# MARI_SCH.net
KiCad netlist of a schematic drawn in EAGLE
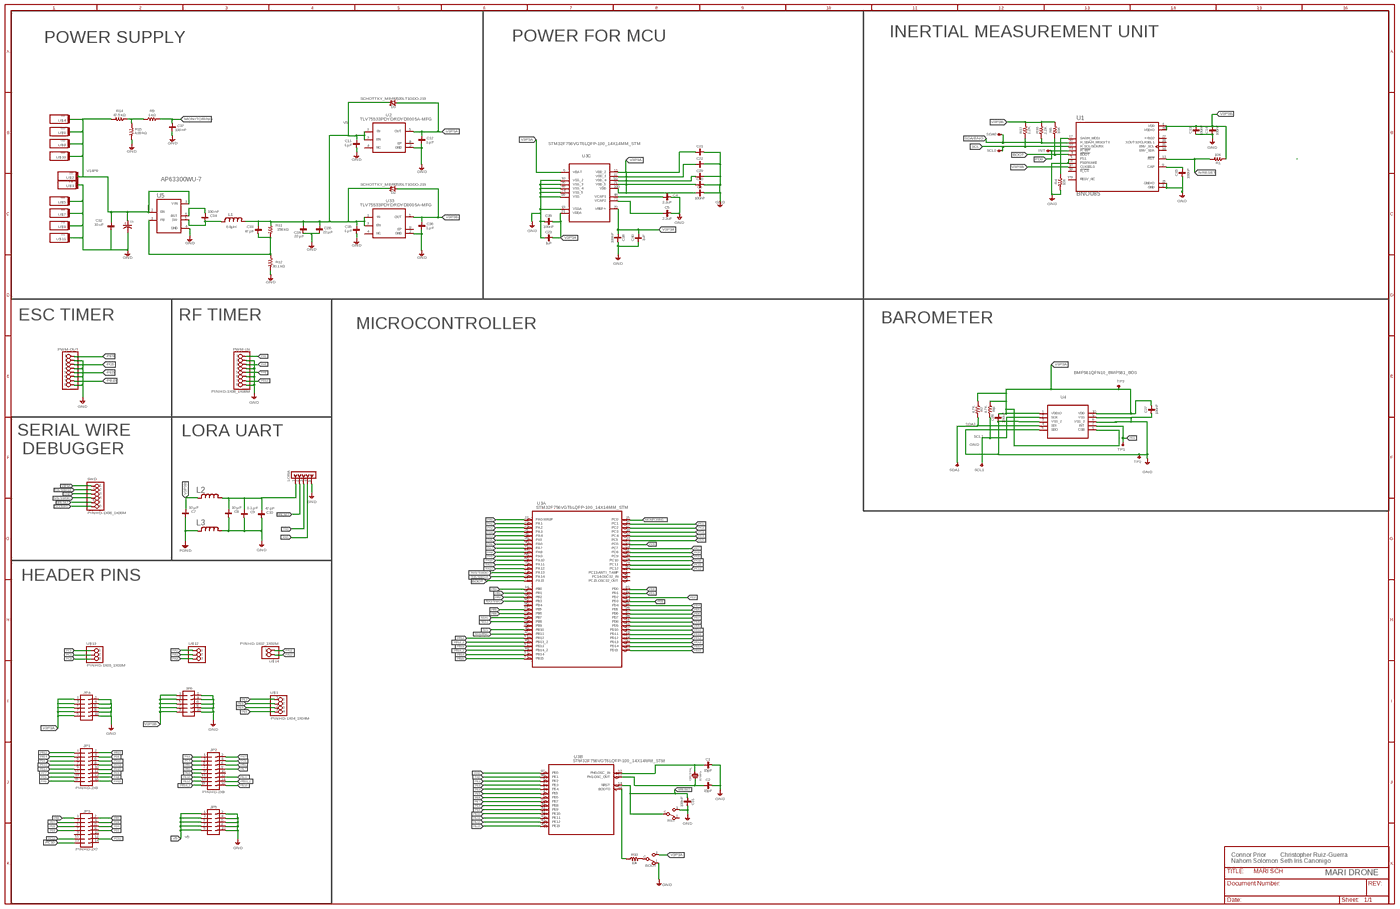
[diagram p0: schematic, sheet 1, overview]
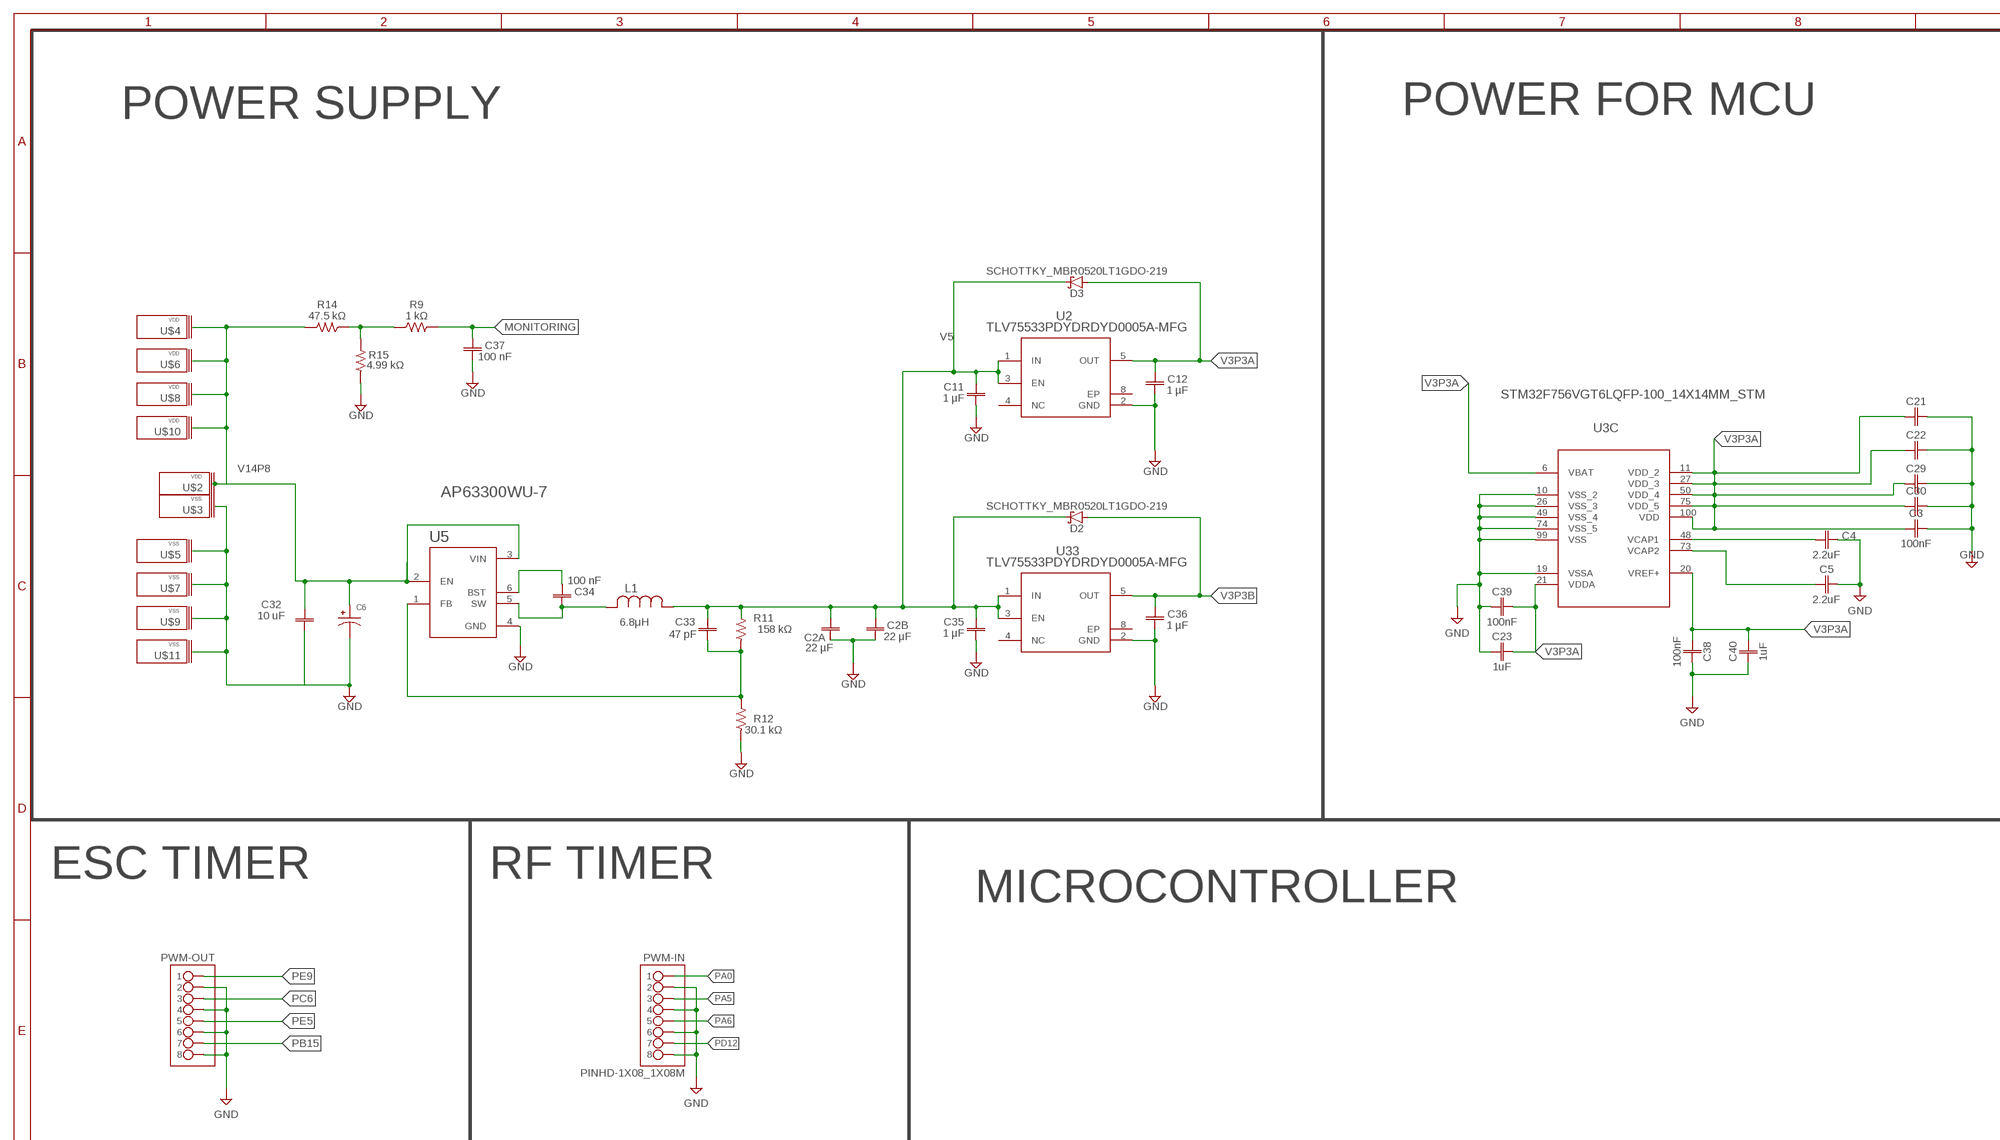
[diagram p1: schematic, sheet 1, part 1 of 4]
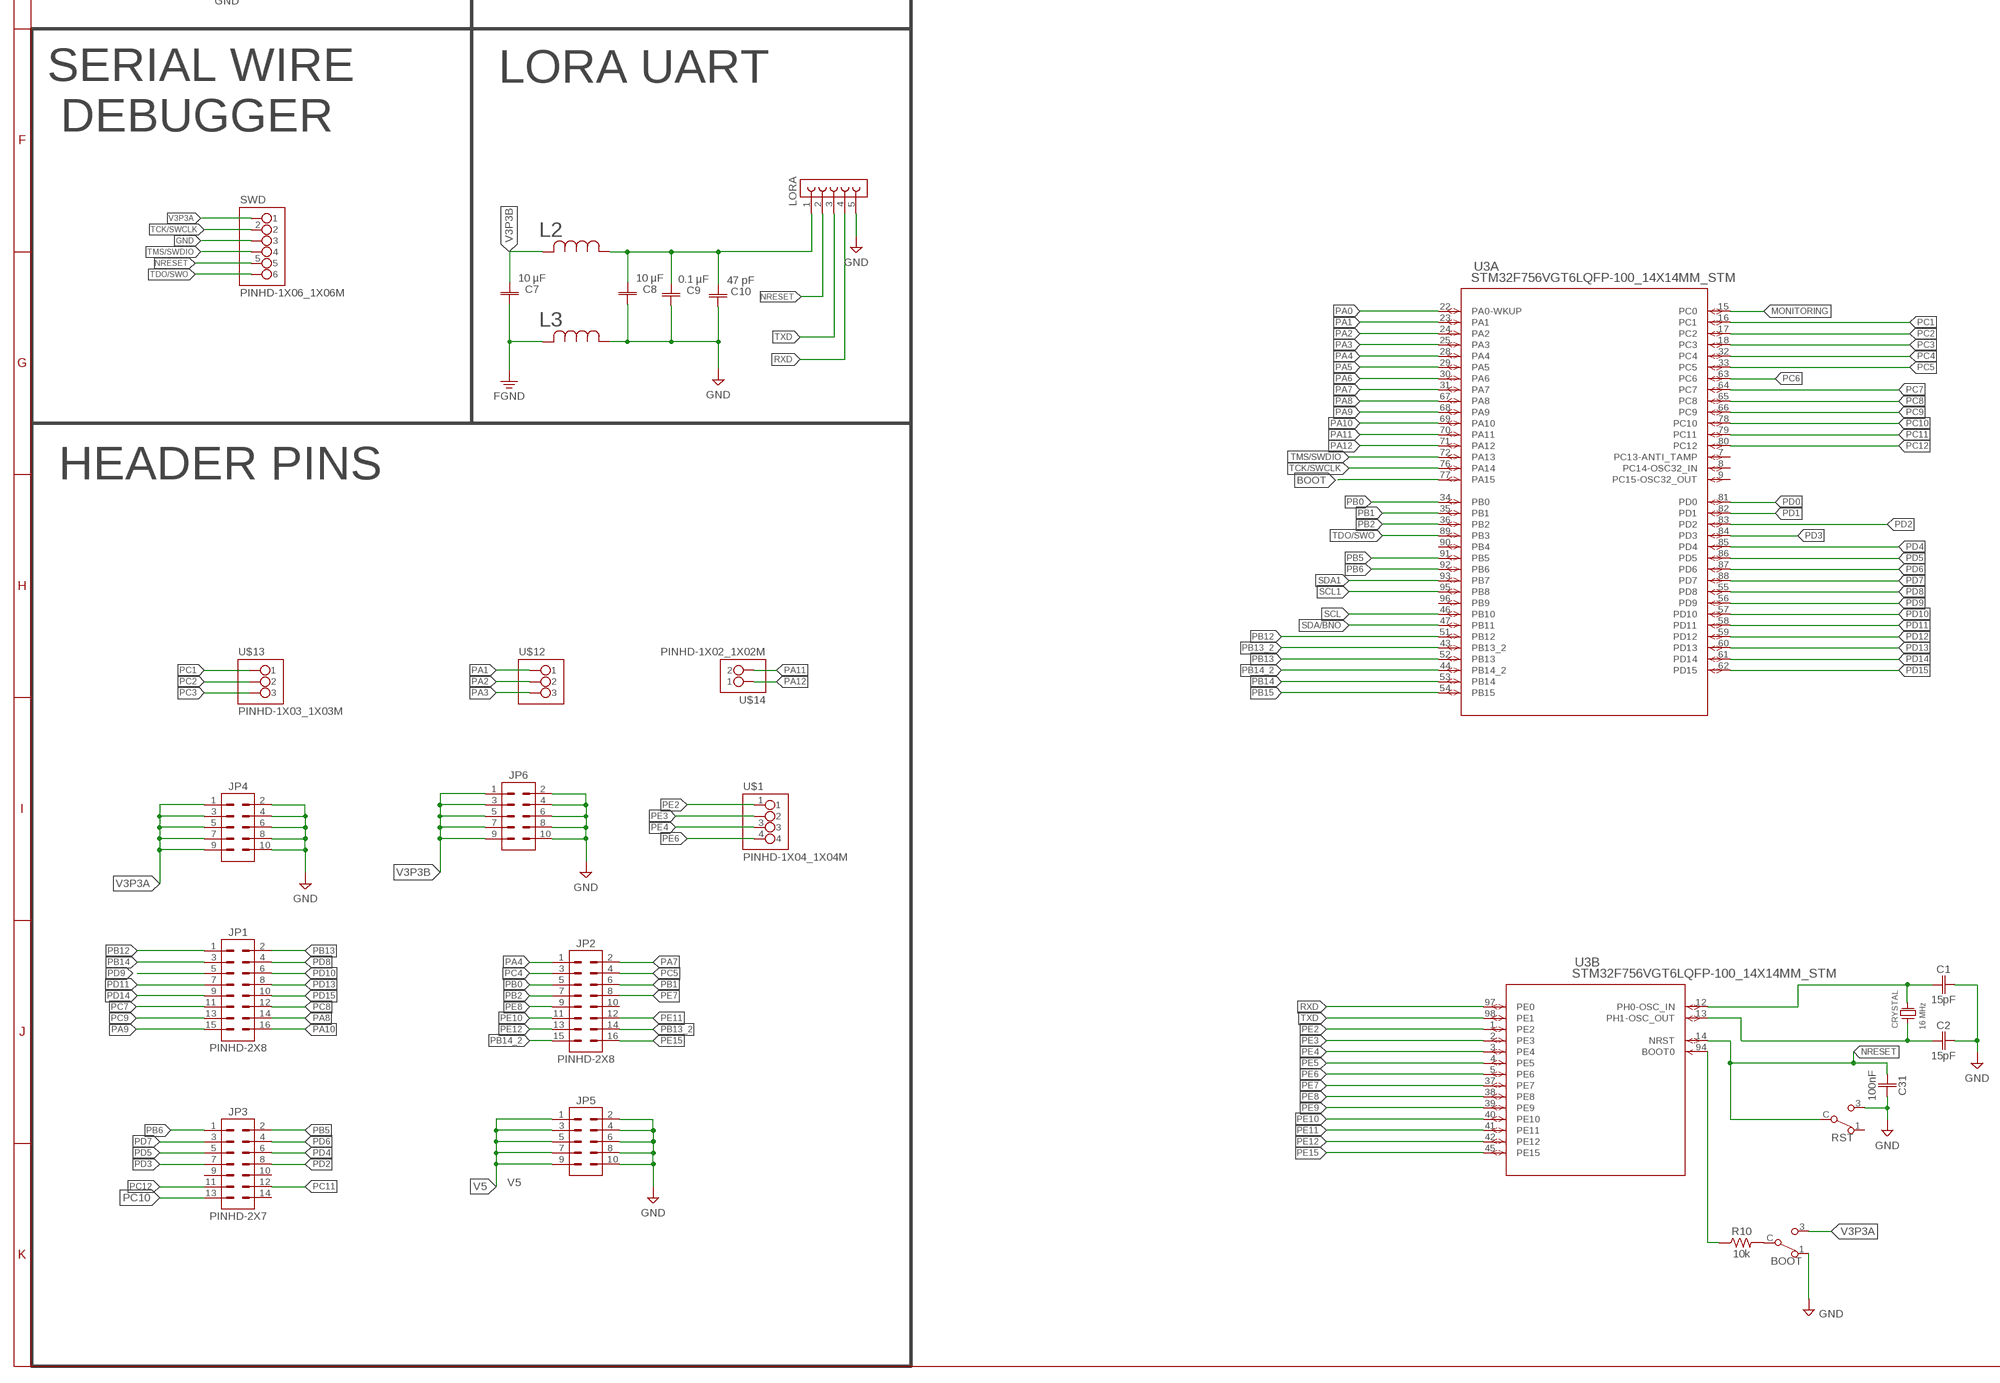
[diagram p2: schematic, sheet 1, part 2 of 4]
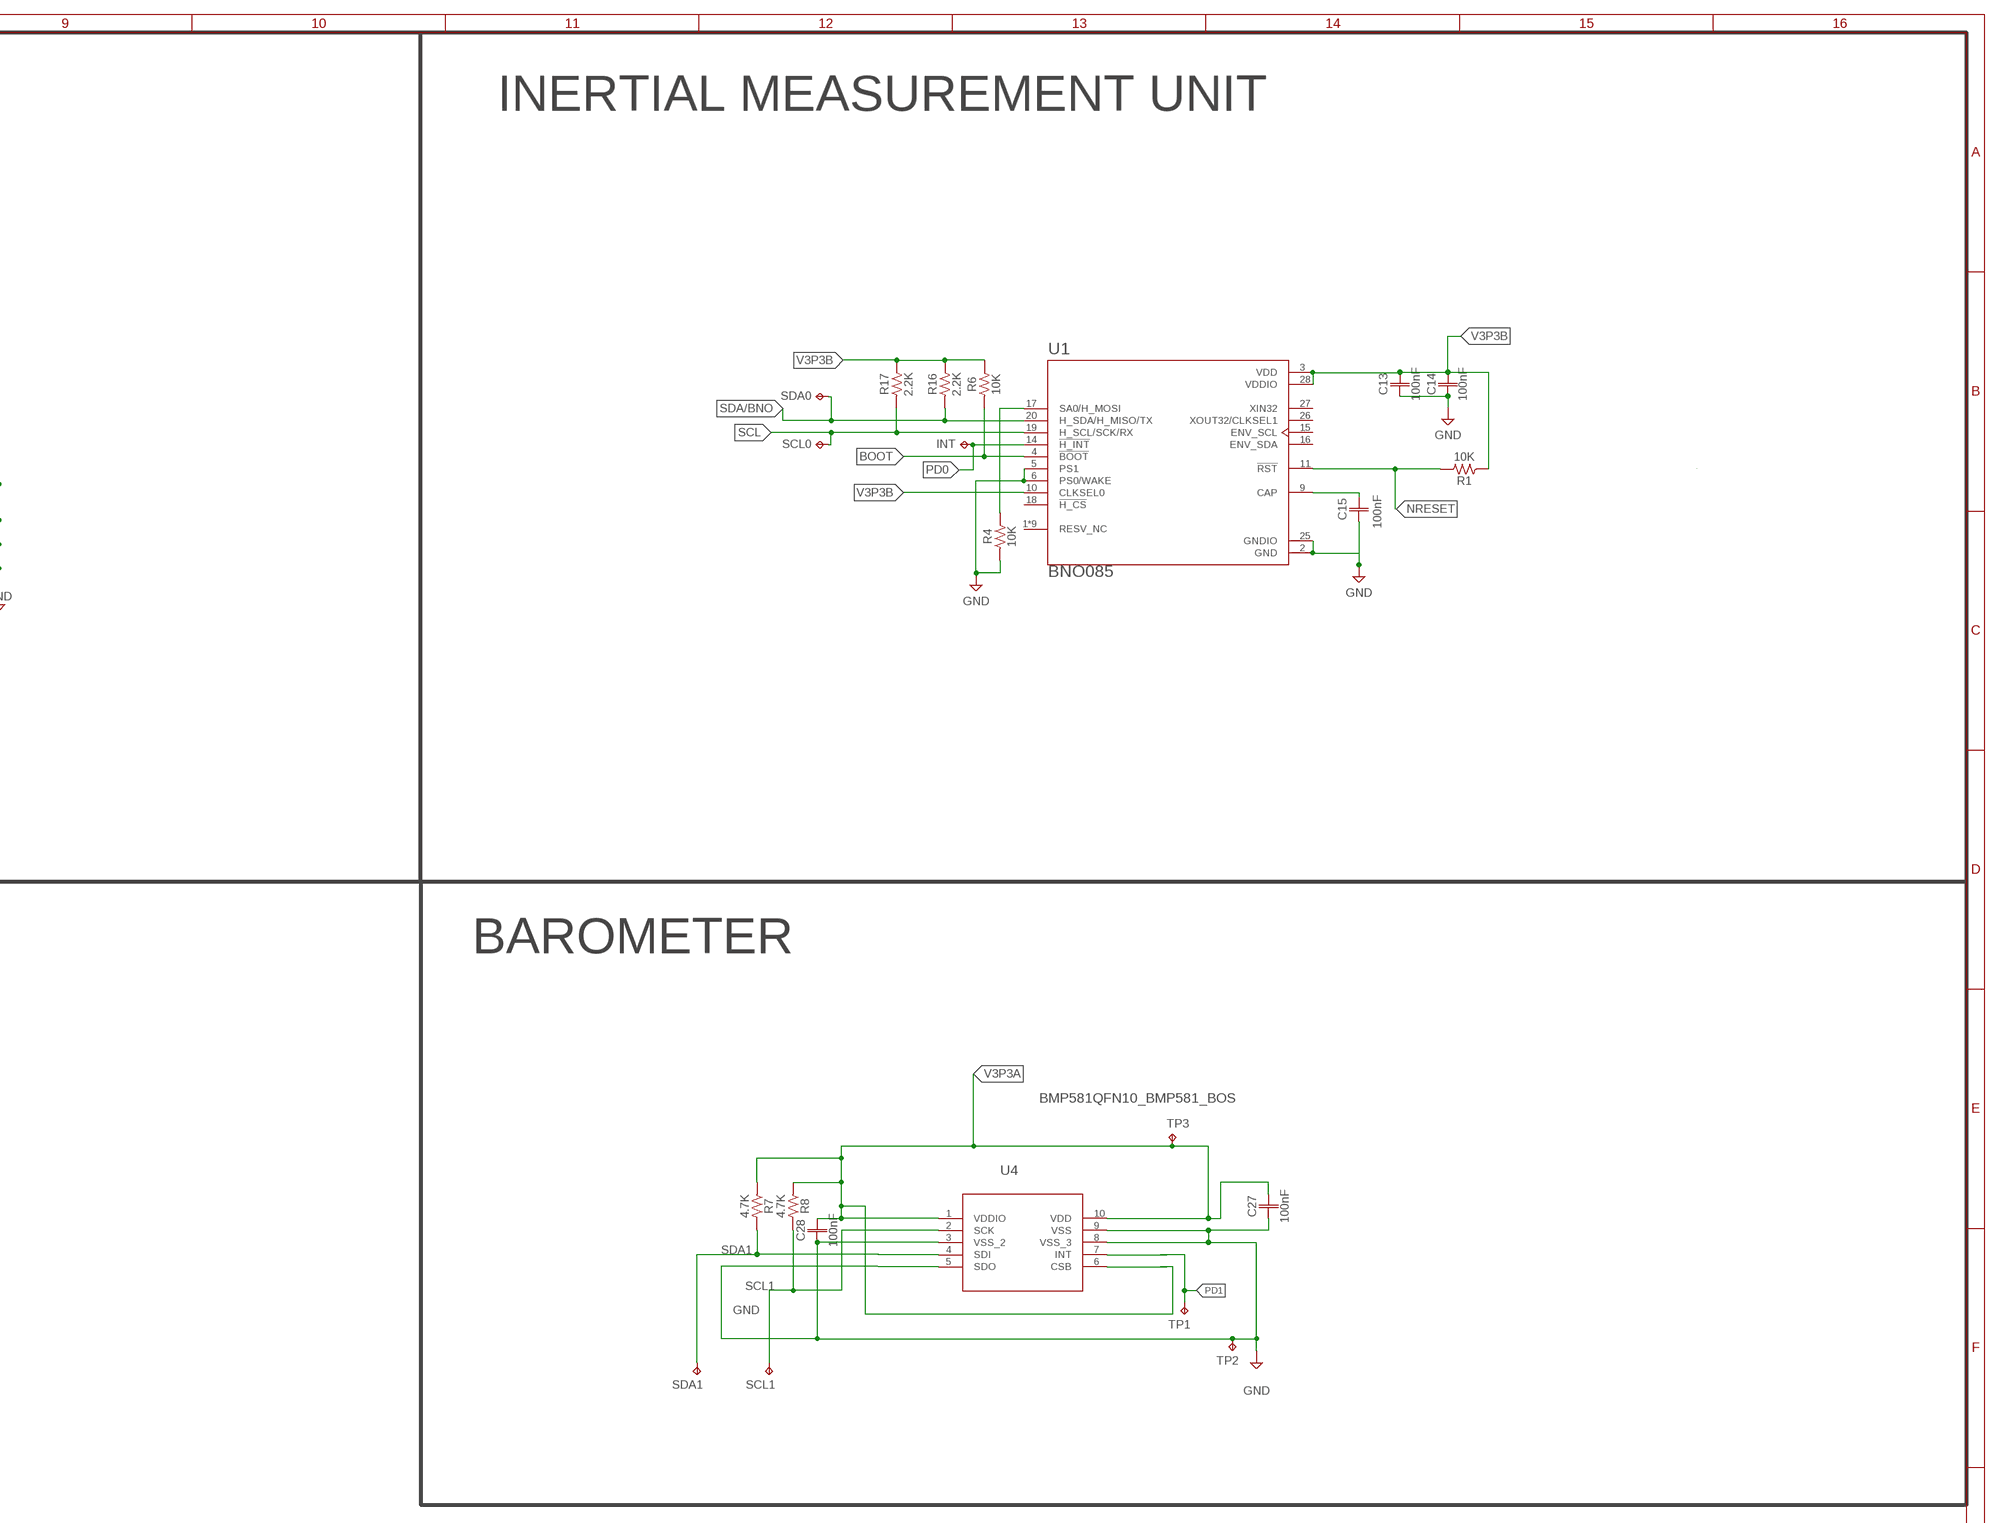
[diagram p3: schematic, sheet 1, part 3 of 4]
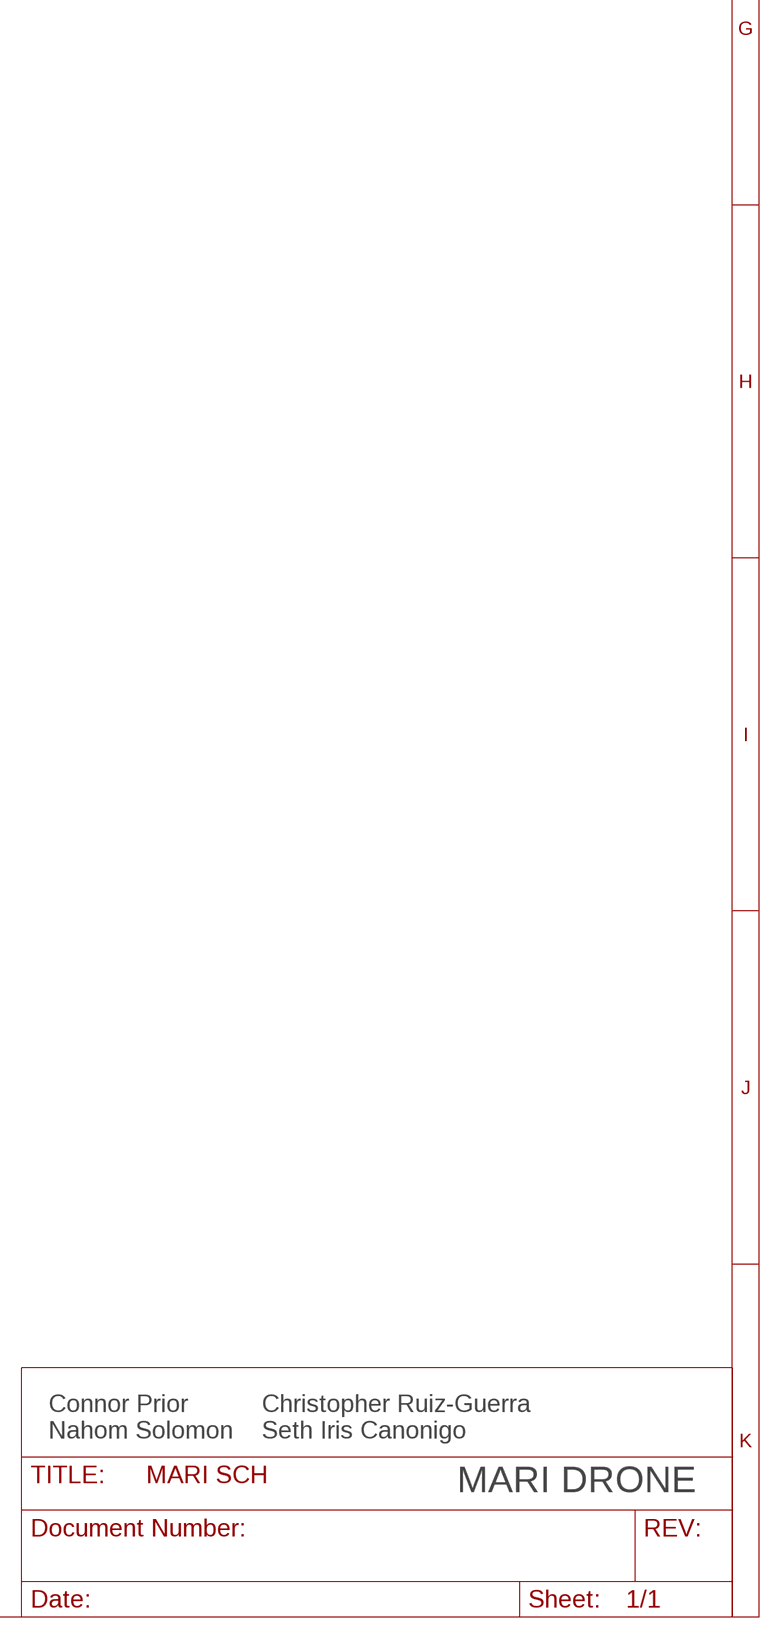
[diagram p4: schematic, sheet 1, part 4 of 4]

(export (version "E")
  (design (tool "Eeschema 10.0.6"))
  (components
    (comp (ref "BOOT")
      (value "SPDT_SWITCH_CL-SB-12B-01T")
      (footprint "eagle-import:CL-SB-12B-01T")
      (fields
        (field (name "MANUFACTURER") "Nidec Components Corporation")
        (field (name "MPN") "CL-SB-12B-01T")
      )
      (libsource (lib "eagle-import") (part "SPDT_SWITCH_CL-SB-12B-01T"))
    )
    (comp (ref "C1")
      (value "15pF")
      (footprint "eagle-import:CAPC1005X60")
      (libsource (lib "eagle-import") (part "CCHIP-0402(1005-METRIC)_"))
    )
    (comp (ref "C2")
      (value "15pF")
      (footprint "eagle-import:CAPC1005X60")
      (libsource (lib "eagle-import") (part "CCHIP-0402(1005-METRIC)_"))
    )
    (comp (ref "C2A")
      (value "22 µF")
      (footprint "eagle-import:CAPC1005X60")
      (libsource (lib "eagle-import") (part "CCHIP-0402(1005-METRIC)_"))
    )
    (comp (ref "C2B")
      (value "22 µF")
      (footprint "eagle-import:CAPC1005X60")
      (libsource (lib "eagle-import") (part "CCHIP-0402(1005-METRIC)_"))
    )
    (comp (ref "C3")
      (value "100nF")
      (footprint "eagle-import:CAPC1005X60")
      (libsource (lib "eagle-import") (part "CCHIP-0402(1005-METRIC)_"))
    )
    (comp (ref "C4")
      (value "2.2uF")
      (footprint "eagle-import:CAPC1005X60")
      (libsource (lib "eagle-import") (part "CCHIP-0402(1005-METRIC)_"))
    )
    (comp (ref "C5")
      (value "2.2uF")
      (footprint "eagle-import:CAPC1005X60")
      (libsource (lib "eagle-import") (part "CCHIP-0402(1005-METRIC)_"))
    )
    (comp (ref "C6")
      (value "B41866C5108M000")
      (footprint "eagle-import:CAPPRD500W60D1250H2200")
      (fields (field (name "MANUFACTURER") "TDK"))
      (libsource (lib "eagle-import") (part "B41866C5108M000"))
    )
    (comp (ref "C7")
      (value "10 µF")
      (footprint "eagle-import:CAPC1005X60")
      (libsource (lib "eagle-import") (part "CCHIP-0402(1005-METRIC)_"))
    )
    (comp (ref "C8")
      (value "10 µF")
      (footprint "eagle-import:CAPC1005X60")
      (libsource (lib "eagle-import") (part "CCHIP-0402(1005-METRIC)_"))
    )
    (comp (ref "C9")
      (value "0.1 µF")
      (footprint "eagle-import:CAPC1005X60")
      (libsource (lib "eagle-import") (part "CCHIP-0402(1005-METRIC)_"))
    )
    (comp (ref "C10")
      (value "47 pF")
      (footprint "eagle-import:CAPC1005X60")
      (libsource (lib "eagle-import") (part "CCHIP-0402(1005-METRIC)_"))
    )
    (comp (ref "C11")
      (value "1 µF")
      (footprint "eagle-import:CAPC1005X60")
      (libsource (lib "eagle-import") (part "CCHIP-0402(1005-METRIC)_"))
    )
    (comp (ref "C12")
      (value "1 µF")
      (footprint "eagle-import:CAPC1005X60")
      (libsource (lib "eagle-import") (part "CCHIP-0402(1005-METRIC)_"))
    )
    (comp (ref "C13")
      (value "100nF")
      (footprint "eagle-import:CAPC1005X60")
      (libsource (lib "eagle-import") (part "CCHIP-0402(1005-METRIC)_"))
    )
    (comp (ref "C14")
      (value "100nF")
      (footprint "eagle-import:CAPC1005X60")
      (libsource (lib "eagle-import") (part "CCHIP-0402(1005-METRIC)_"))
    )
    (comp (ref "C15")
      (value "100nF")
      (footprint "eagle-import:CAPC1005X60")
      (libsource (lib "eagle-import") (part "CCHIP-0402(1005-METRIC)_"))
    )
    (comp (ref "C21")
      (value "100nF")
      (footprint "eagle-import:CAPC1005X60")
      (libsource (lib "eagle-import") (part "CCHIP-0402(1005-METRIC)_"))
    )
    (comp (ref "C22")
      (value "100nF")
      (footprint "eagle-import:CAPC1005X60")
      (libsource (lib "eagle-import") (part "CCHIP-0402(1005-METRIC)_"))
    )
    (comp (ref "C23")
      (value "1uF")
      (footprint "eagle-import:CAPC1005X60")
      (libsource (lib "eagle-import") (part "CCHIP-0402(1005-METRIC)_"))
    )
    (comp (ref "C27")
      (value "100nF")
      (footprint "eagle-import:CAPC1005X60")
      (libsource (lib "eagle-import") (part "CCHIP-0402(1005-METRIC)_"))
    )
    (comp (ref "C28")
      (value "100nF")
      (footprint "eagle-import:CAPC1005X60")
      (libsource (lib "eagle-import") (part "CCHIP-0402(1005-METRIC)_"))
    )
    (comp (ref "C29")
      (value "100nF")
      (footprint "eagle-import:CAPC1005X60")
      (libsource (lib "eagle-import") (part "CCHIP-0402(1005-METRIC)_"))
    )
    (comp (ref "C30")
      (value "100nF")
      (footprint "eagle-import:CAPC1005X60")
      (libsource (lib "eagle-import") (part "CCHIP-0402(1005-METRIC)_"))
    )
    (comp (ref "C31")
      (value "100nF")
      (footprint "eagle-import:CAPC1005X60")
      (libsource (lib "eagle-import") (part "CCHIP-0402(1005-METRIC)_"))
    )
    (comp (ref "C32")
      (value "10 uF")
      (footprint "eagle-import:CAPC2012X110")
      (libsource (lib "eagle-import") (part "CCHIP-0805(2012-METRIC)_"))
    )
    (comp (ref "C33")
      (value "47 pF")
      (footprint "eagle-import:CAPC1005X60")
      (libsource (lib "eagle-import") (part "CCHIP-0402(1005-METRIC)_"))
    )
    (comp (ref "C34")
      (value "100 nF")
      (footprint "eagle-import:CAPC1005X60")
      (libsource (lib "eagle-import") (part "CCHIP-0402(1005-METRIC)_"))
    )
    (comp (ref "C35")
      (value "1 µF")
      (footprint "eagle-import:CAPC1005X60")
      (libsource (lib "eagle-import") (part "CCHIP-0402(1005-METRIC)_"))
    )
    (comp (ref "C36")
      (value "1 µF")
      (footprint "eagle-import:CAPC1005X60")
      (libsource (lib "eagle-import") (part "CCHIP-0402(1005-METRIC)_"))
    )
    (comp (ref "C37")
      (value "100 nF")
      (footprint "eagle-import:CAPC1005X60")
      (libsource (lib "eagle-import") (part "CCHIP-0402(1005-METRIC)_"))
    )
    (comp (ref "C38")
      (value "100nF")
      (footprint "eagle-import:CAPC1005X60")
      (libsource (lib "eagle-import") (part "CCHIP-0402(1005-METRIC)_"))
    )
    (comp (ref "C39")
      (value "100nF")
      (footprint "eagle-import:CAPC1005X60")
      (libsource (lib "eagle-import") (part "CCHIP-0402(1005-METRIC)_"))
    )
    (comp (ref "C40")
      (value "1uF")
      (footprint "eagle-import:CAPC1005X60")
      (libsource (lib "eagle-import") (part "CCHIP-0402(1005-METRIC)_"))
    )
    (comp (ref "CRYSTAL")
      (value "16 MHz")
      (footprint "eagle-import:STDCRG1-16M")
      (libsource (lib "eagle-import") (part "STDCRG1-16M"))
    )
    (comp (ref "D2")
      (value "SCHOTTKY_MBR0520LT1GDO-219")
      (footprint "eagle-import:SODFL3718X115")
      (fields (field (name "MANUFACTURER") "onsemi") (field (name "MPN") "MBR0520LT1G"))
      (libsource (lib "eagle-import") (part "SCHOTTKY_DO-219MBR0520LT1G"))
    )
    (comp (ref "D3")
      (value "SCHOTTKY_MBR0520LT1GDO-219")
      (footprint "eagle-import:SODFL3718X115")
      (fields (field (name "MANUFACTURER") "onsemi") (field (name "MPN") "MBR0520LT1G"))
      (libsource (lib "eagle-import") (part "SCHOTTKY_DO-219MBR0520LT1G"))
    )
    (comp (ref "INT")
      (value "TPB1,27")
      (footprint "eagle-import:B1,27")
      (libsource (lib "eagle-import") (part "TPB1,27"))
    )
    (comp (ref "JP1")
      (value "PINHD-2X8")
      (footprint "eagle-import:2X08")
      (libsource (lib "eagle-import") (part "PINHD-2X8"))
    )
    (comp (ref "JP2")
      (value "PINHD-2X8")
      (footprint "eagle-import:2X08")
      (libsource (lib "eagle-import") (part "PINHD-2X8"))
    )
    (comp (ref "JP3")
      (value "PINHD-2X7")
      (footprint "eagle-import:2X07")
      (libsource (lib "eagle-import") (part "PINHD-2X7"))
    )
    (comp (ref "JP4")
      (value "PINHD-2X5")
      (footprint "eagle-import:2X05")
      (libsource (lib "eagle-import") (part "PINHD-2X5"))
    )
    (comp (ref "JP5")
      (value "PINHD-2X5")
      (footprint "eagle-import:2X05")
      (libsource (lib "eagle-import") (part "PINHD-2X5"))
    )
    (comp (ref "JP6")
      (value "PINHD-2X5")
      (footprint "eagle-import:2X05")
      (libsource (lib "eagle-import") (part "PINHD-2X5"))
    )
    (comp (ref "L1")
      (value "74437334068IND_WE-LHMI_5020_WRE")
      (footprint "eagle-import:IND_WE-LHMI_5020_WRE")
      (fields
        (field (name "MANUFACTURER_PART_NUMBER") "74437334068")
        (field (name "COPYRIGHT") "Copyright (C) 2026 Ultra Librarian. All rights reserved.")
      )
      (libsource (lib "eagle-import") (part "74437334068IND_WE-LHMI_5020_WRE"))
    )
    (comp (ref "L2")
      (value "BLM15EG121SN1DIND_BLM15_0402_MUR-M")
      (footprint "eagle-import:IND_BLM15_0402_MUR-M")
      (fields
        (field (name "MANUFACTURER_PART_NUMBER") "BLM15EG121SN1D")
        (field (name "COPYRIGHT") "Copyright (C) 2026 Ultra Librarian. All rights reserved.")
      )
      (libsource (lib "eagle-import") (part "BLM15EG121SN1DIND_BLM15_0402_MUR-M"))
    )
    (comp (ref "L3")
      (value "BLM15EG121SN1DIND_BLM15_0402_MUR-M")
      (footprint "eagle-import:IND_BLM15_0402_MUR-M")
      (fields
        (field (name "MANUFACTURER_PART_NUMBER") "BLM15EG121SN1D")
        (field (name "COPYRIGHT") "Copyright (C) 2026 Ultra Librarian. All rights reserved.")
      )
      (libsource (lib "eagle-import") (part "BLM15EG121SN1DIND_BLM15_0402_MUR-M"))
    )
    (comp (ref "LORA")
      (value "FEMALE-HEADER-1X5")
      (footprint "eagle-import:1X05")
      (libsource (lib "eagle-import") (part "FEMALE-HEADER-1X5"))
    )
    (comp (ref "PWM-IN")
      (value "PINHD-1X08_1X08M")
      (footprint "eagle-import:1X08")
      (libsource (lib "eagle-import") (part "PINHD-1X08_1X08M"))
    )
    (comp (ref "PWM-OUT")
      (value "PINHD-1X08_1X08M")
      (footprint "eagle-import:1X08")
      (libsource (lib "eagle-import") (part "PINHD-1X08_1X08M"))
    )
    (comp (ref "R1")
      (value "10K")
      (footprint "eagle-import:RESC1005X40")
      (libsource (lib "eagle-import") (part "R-USCHIP-0402(1005-METRIC)_"))
    )
    (comp (ref "R4")
      (value "10K")
      (footprint "eagle-import:RESC1005X40")
      (libsource (lib "eagle-import") (part "R-USCHIP-0402(1005-METRIC)_"))
    )
    (comp (ref "R6")
      (value "10K")
      (footprint "eagle-import:RESC1005X40")
      (libsource (lib "eagle-import") (part "R-USCHIP-0402(1005-METRIC)_"))
    )
    (comp (ref "R7")
      (value "4.7K")
      (footprint "eagle-import:RESC1005X40")
      (libsource (lib "eagle-import") (part "R-USCHIP-0402(1005-METRIC)_"))
    )
    (comp (ref "R8")
      (value "4.7K")
      (footprint "eagle-import:RESC1005X40")
      (libsource (lib "eagle-import") (part "R-USCHIP-0402(1005-METRIC)_"))
    )
    (comp (ref "R9")
      (value "1 kΩ")
      (footprint "eagle-import:RESC1005X40")
      (libsource (lib "eagle-import") (part "R-USCHIP-0402(1005-METRIC)_"))
    )
    (comp (ref "R10")
      (value "10k")
      (footprint "eagle-import:RESC1005X40")
      (libsource (lib "eagle-import") (part "R-USCHIP-0402(1005-METRIC)_"))
    )
    (comp (ref "R11")
      (value "158 kΩ")
      (footprint "eagle-import:RESC1005X40")
      (libsource (lib "eagle-import") (part "R-USCHIP-0402(1005-METRIC)_"))
    )
    (comp (ref "R12")
      (value "30.1 kΩ")
      (footprint "eagle-import:RESC1005X40")
      (libsource (lib "eagle-import") (part "R-USCHIP-0402(1005-METRIC)_"))
    )
    (comp (ref "R14")
      (value "47.5 kΩ")
      (footprint "eagle-import:RESC1005X40")
      (libsource (lib "eagle-import") (part "R-USCHIP-0402(1005-METRIC)_"))
    )
    (comp (ref "R15")
      (value "4.99 kΩ")
      (footprint "eagle-import:RESC1005X40")
      (libsource (lib "eagle-import") (part "R-USCHIP-0402(1005-METRIC)_"))
    )
    (comp (ref "R16")
      (value "2.2K")
      (footprint "eagle-import:RESC1005X40")
      (libsource (lib "eagle-import") (part "R-USCHIP-0402(1005-METRIC)_"))
    )
    (comp (ref "R17")
      (value "2.2K")
      (footprint "eagle-import:RESC1005X40")
      (libsource (lib "eagle-import") (part "R-USCHIP-0402(1005-METRIC)_"))
    )
    (comp (ref "RST")
      (value "SPDT_SWITCH_CL-SB-12B-01T")
      (footprint "eagle-import:CL-SB-12B-01T")
      (fields
        (field (name "MANUFACTURER") "Nidec Components Corporation")
        (field (name "MPN") "CL-SB-12B-01T")
      )
      (libsource (lib "eagle-import") (part "SPDT_SWITCH_CL-SB-12B-01T"))
    )
    (comp (ref "SCL0")
      (value "TPB1,27")
      (footprint "eagle-import:B1,27")
      (libsource (lib "eagle-import") (part "TPB1,27"))
    )
    (comp (ref "SCL1")
      (value "TPB1,27")
      (footprint "eagle-import:B1,27")
      (libsource (lib "eagle-import") (part "TPB1,27"))
    )
    (comp (ref "SDA0")
      (value "TPB1,27")
      (footprint "eagle-import:B1,27")
      (libsource (lib "eagle-import") (part "TPB1,27"))
    )
    (comp (ref "SDA1")
      (value "TPB1,27")
      (footprint "eagle-import:B1,27")
      (libsource (lib "eagle-import") (part "TPB1,27"))
    )
    (comp (ref "SWD")
      (value "PINHD-1X06_1X06M")
      (footprint "eagle-import:1X06")
      (libsource (lib "eagle-import") (part "PINHD-1X06_1X06M"))
    )
    (comp (ref "TP1")
      (value "TPB1,27")
      (footprint "eagle-import:B1,27")
      (libsource (lib "eagle-import") (part "TPB1,27"))
    )
    (comp (ref "TP2")
      (value "TPB1,27")
      (footprint "eagle-import:B1,27")
      (libsource (lib "eagle-import") (part "TPB1,27"))
    )
    (comp (ref "TP3")
      (value "TPB1,27")
      (footprint "eagle-import:B1,27")
      (libsource (lib "eagle-import") (part "TPB1,27"))
    )
    (comp (ref "U$1")
      (value "PINHD-1X04_1X04M")
      (footprint "eagle-import:1X04")
      (libsource (lib "eagle-import") (part "PINHD-1X04_1X04M"))
    )
    (comp (ref "U$2")
      (value "VDD")
      (footprint "eagle-import:4MM_PLUG")
      (libsource (lib "eagle-import") (part "4MM_FEMALE_VDD"))
    )
    (comp (ref "U$3")
      (value "VSS")
      (footprint "eagle-import:4MM_PLUG")
      (libsource (lib "eagle-import") (part "4MM_FEMALE_VSS"))
    )
    (comp (ref "U$4")
      (value "VDD")
      (footprint "eagle-import:4MM_PLUG")
      (libsource (lib "eagle-import") (part "4MM_FEMALE_VDD"))
    )
    (comp (ref "U$5")
      (value "VSS")
      (footprint "eagle-import:4MM_PLUG")
      (libsource (lib "eagle-import") (part "4MM_FEMALE_VSS"))
    )
    (comp (ref "U$6")
      (value "VDD")
      (footprint "eagle-import:4MM_PLUG")
      (libsource (lib "eagle-import") (part "4MM_FEMALE_VDD"))
    )
    (comp (ref "U$7")
      (value "VSS")
      (footprint "eagle-import:4MM_PLUG")
      (libsource (lib "eagle-import") (part "4MM_FEMALE_VSS"))
    )
    (comp (ref "U$8")
      (value "VDD")
      (footprint "eagle-import:4MM_PLUG")
      (libsource (lib "eagle-import") (part "4MM_FEMALE_VDD"))
    )
    (comp (ref "U$9")
      (value "VSS")
      (footprint "eagle-import:4MM_PLUG")
      (libsource (lib "eagle-import") (part "4MM_FEMALE_VSS"))
    )
    (comp (ref "U$10")
      (value "VDD")
      (footprint "eagle-import:4MM_PLUG")
      (libsource (lib "eagle-import") (part "4MM_FEMALE_VDD"))
    )
    (comp (ref "U$11")
      (value "VSS")
      (footprint "eagle-import:4MM_PLUG")
      (libsource (lib "eagle-import") (part "4MM_FEMALE_VSS"))
    )
    (comp (ref "U$12")
      (value "PINHD-1X03_1X03M")
      (footprint "eagle-import:1X03")
      (libsource (lib "eagle-import") (part "PINHD-1X03_1X03M"))
    )
    (comp (ref "U$13")
      (value "PINHD-1X03_1X03M")
      (footprint "eagle-import:1X03")
      (libsource (lib "eagle-import") (part "PINHD-1X03_1X03M"))
    )
    (comp (ref "U$14")
      (value "PINHD-1X02_1X02M")
      (footprint "eagle-import:1X02")
      (libsource (lib "eagle-import") (part "PINHD-1X02_1X02M"))
    )
    (comp (ref "U1")
      (value "BNO085")
      (footprint "eagle-import:IC_BNO085")
      (fields (field (name "MF") "Hillcrest Laboratories,"))
      (libsource (lib "eagle-import") (part "BNO085"))
    )
    (comp (ref "U2")
      (value "TLV75533PDYDRDYD0005A-MFG")
      (footprint "eagle-import:DYD0005A-MFG")
      (fields
        (field (name "MANUFACTURER_PART_NUMBER") "TLV75533PDYDR")
        (field (name "COPYRIGHT") "Copyright (C) 2025 Ultra Librarian. All rights reserved.")
      )
      (libsource (lib "eagle-import") (part "TLV75533PDYDRDYD0005A-MFG"))
    )
    (comp (ref "U3")
      (value "STM32F756VGT6LQFP-100_14X14MM_STM")
      (footprint "eagle-import:LQFP-100_14X14MM_STM")
      (fields
        (field (name "MANUFACTURER_PART_NUMBER") "STM32F756VGT6")
        (field (name "COPYRIGHT") "Copyright (C) 2025 Ultra Librarian. All rights reserved.")
      )
      (libsource (lib "eagle-import") (part "STM32F756VGT6LQFP-100_14X14MM_STM"))
    )
    (comp (ref "U4")
      (value "BMP581QFN10_BMP581_BOS")
      (footprint "eagle-import:QFN10_BMP581_BOS")
      (fields
        (field (name "MANUFACTURER_PART_NUMBER") "BMP581")
        (field (name "COPYRIGHT") "Copyright (C) 2026 Ultra Librarian. All rights reserved.")
      )
      (libsource (lib "eagle-import") (part "BMP581QFN10_BMP581_BOS"))
    )
    (comp (ref "U5")
      (value "AP63300WU-7")
      (footprint "eagle-import:SOT95P280X100-6N")
      (fields (field (name "MANUFACTURER") "DIODES"))
      (libsource (lib "eagle-import") (part "AP63300WU-7"))
    )
    (comp (ref "U33")
      (value "TLV75533PDYDRDYD0005A-MFG")
      (footprint "eagle-import:DYD0005A-MFG")
      (fields
        (field (name "MANUFACTURER_PART_NUMBER") "TLV75533PDYDR")
        (field (name "COPYRIGHT") "Copyright (C) 2025 Ultra Librarian. All rights reserved.")
      )
      (libsource (lib "eagle-import") (part "TLV75533PDYDRDYD0005A-MFG"))
    )
  )
  (nets
    (net (code "1") (name "/V14P8") (class "Default")
      (node (ref "C32") (pin "2") (pinfunction "2_2") (pintype "passive"))
      (node (ref "C6") (pin "1") (pinfunction "1_1") (pintype "passive"))
      (node (ref "R14") (pin "2") (pinfunction "2_2") (pintype "passive"))
      (node (ref "U$10") (pin "P$1") (pinfunction "P$1_P$1") (pintype "bidirectional"))
      (node (ref "U$2") (pin "P$1") (pinfunction "P$1_P$1") (pintype "bidirectional"))
      (node (ref "U$4") (pin "P$1") (pinfunction "P$1_P$1") (pintype "bidirectional"))
      (node (ref "U$6") (pin "P$1") (pinfunction "P$1_P$1") (pintype "bidirectional"))
      (node (ref "U$8") (pin "P$1") (pinfunction "P$1_P$1") (pintype "bidirectional"))
      (node (ref "U5") (pin "2") (pinfunction "EN_2") (pintype "input"))
      (node (ref "U5") (pin "3") (pinfunction "VIN_3") (pintype "power_in"))
    )
    (net (code "2") (name "BOOT") (class "Default")
      (node (ref "R6") (pin "1") (pinfunction "1_1") (pintype "passive"))
      (node (ref "U1") (pin "4") (pinfunction "~{BOOT}_4") (pintype "input"))
      (node (ref "U3") (pin "77") (pinfunction "PA15_77") (pintype "bidirectional"))
    )
    (net (code "3") (name "FGND") (class "Default")
      (node (ref "C7") (pin "1") (pinfunction "1_1") (pintype "passive"))
      (node (ref "L3") (pin "2") (pinfunction "2_2") (pintype "passive"))
    )
    (net (code "4") (name "GND") (class "Default")
      (node (ref "BOOT") (pin "1") (pinfunction "NC_1") (pintype "passive"))
      (node (ref "C1") (pin "2") (pinfunction "2_2") (pintype "passive"))
      (node (ref "C10") (pin "1") (pinfunction "1_1") (pintype "passive"))
      (node (ref "C11") (pin "1") (pinfunction "1_1") (pintype "passive"))
      (node (ref "C12") (pin "1") (pinfunction "1_1") (pintype "passive"))
      (node (ref "C13") (pin "1") (pinfunction "1_1") (pintype "passive"))
      (node (ref "C14") (pin "1") (pinfunction "1_1") (pintype "passive"))
      (node (ref "C15") (pin "1") (pinfunction "1_1") (pintype "passive"))
      (node (ref "C2") (pin "2") (pinfunction "2_2") (pintype "passive"))
      (node (ref "C21") (pin "2") (pinfunction "2_2") (pintype "passive"))
      (node (ref "C22") (pin "2") (pinfunction "2_2") (pintype "passive"))
      (node (ref "C23") (pin "1") (pinfunction "1_1") (pintype "passive"))
      (node (ref "C27") (pin "1") (pinfunction "1_1") (pintype "passive"))
      (node (ref "C28") (pin "1") (pinfunction "1_1") (pintype "passive"))
      (node (ref "C29") (pin "2") (pinfunction "2_2") (pintype "passive"))
      (node (ref "C2A") (pin "2") (pinfunction "2_2") (pintype "passive"))
      (node (ref "C2B") (pin "2") (pinfunction "2_2") (pintype "passive"))
      (node (ref "C3") (pin "2") (pinfunction "2_2") (pintype "passive"))
      (node (ref "C30") (pin "2") (pinfunction "2_2") (pintype "passive"))
      (node (ref "C31") (pin "2") (pinfunction "2_2") (pintype "passive"))
      (node (ref "C32") (pin "1") (pinfunction "1_1") (pintype "passive"))
      (node (ref "C35") (pin "1") (pinfunction "1_1") (pintype "passive"))
      (node (ref "C36") (pin "1") (pinfunction "1_1") (pintype "passive"))
      (node (ref "C37") (pin "2") (pinfunction "2_2") (pintype "passive"))
      (node (ref "C38") (pin "2") (pinfunction "2_2") (pintype "passive"))
      (node (ref "C39") (pin "1") (pinfunction "1_1") (pintype "passive"))
      (node (ref "C4") (pin "2") (pinfunction "2_2") (pintype "passive"))
      (node (ref "C40") (pin "1") (pinfunction "1_1") (pintype "passive"))
      (node (ref "C5") (pin "2") (pinfunction "2_2") (pintype "passive"))
      (node (ref "C6") (pin "2") (pinfunction "2_2") (pintype "passive"))
      (node (ref "C8") (pin "1") (pinfunction "1_1") (pintype "passive"))
      (node (ref "C9") (pin "1") (pinfunction "1_1") (pintype "passive"))
      (node (ref "JP4") (pin "10") (pinfunction "10_10") (pintype "passive"))
      (node (ref "JP4") (pin "2") (pinfunction "2_2") (pintype "passive"))
      (node (ref "JP4") (pin "4") (pinfunction "4_4") (pintype "passive"))
      (node (ref "JP4") (pin "6") (pinfunction "6_6") (pintype "passive"))
      (node (ref "JP4") (pin "8") (pinfunction "8_8") (pintype "passive"))
      (node (ref "JP5") (pin "10") (pinfunction "10_10") (pintype "passive"))
      (node (ref "JP5") (pin "2") (pinfunction "2_2") (pintype "passive"))
      (node (ref "JP5") (pin "4") (pinfunction "4_4") (pintype "passive"))
      (node (ref "JP5") (pin "6") (pinfunction "6_6") (pintype "passive"))
      (node (ref "JP5") (pin "8") (pinfunction "8_8") (pintype "passive"))
      (node (ref "JP6") (pin "10") (pinfunction "10_10") (pintype "passive"))
      (node (ref "JP6") (pin "2") (pinfunction "2_2") (pintype "passive"))
      (node (ref "JP6") (pin "4") (pinfunction "4_4") (pintype "passive"))
      (node (ref "JP6") (pin "6") (pinfunction "6_6") (pintype "passive"))
      (node (ref "JP6") (pin "8") (pinfunction "8_8") (pintype "passive"))
      (node (ref "L3") (pin "1") (pinfunction "1_1") (pintype "passive"))
      (node (ref "LORA") (pin "5") (pinfunction "5_5") (pintype "passive"))
      (node (ref "PWM-IN") (pin "2") (pinfunction "2_2") (pintype "bidirectional"))
      (node (ref "PWM-IN") (pin "4") (pinfunction "4_4") (pintype "bidirectional"))
      (node (ref "PWM-IN") (pin "6") (pinfunction "6_6") (pintype "bidirectional"))
      (node (ref "PWM-IN") (pin "8") (pinfunction "8_8") (pintype "bidirectional"))
      (node (ref "PWM-OUT") (pin "2") (pinfunction "2_2") (pintype "bidirectional"))
      (node (ref "PWM-OUT") (pin "4") (pinfunction "4_4") (pintype "bidirectional"))
      (node (ref "PWM-OUT") (pin "6") (pinfunction "6_6") (pintype "bidirectional"))
      (node (ref "PWM-OUT") (pin "8") (pinfunction "8_8") (pintype "bidirectional"))
      (node (ref "R12") (pin "1") (pinfunction "1_1") (pintype "passive"))
      (node (ref "R15") (pin "1") (pinfunction "1_1") (pintype "passive"))
      (node (ref "R4") (pin "1") (pinfunction "1_1") (pintype "passive"))
      (node (ref "RST") (pin "3") (pinfunction "NO_3") (pintype "passive"))
      (node (ref "SWD") (pin "3") (pinfunction "3_3") (pintype "bidirectional"))
      (node (ref "TP2") (pin "TP") (pinfunction "TP_TP") (pintype "input"))
      (node (ref "U$11") (pin "P$1") (pinfunction "P$1_P$1") (pintype "bidirectional"))
      (node (ref "U$3") (pin "P$1") (pinfunction "P$1_P$1") (pintype "bidirectional"))
      (node (ref "U$5") (pin "P$1") (pinfunction "P$1_P$1") (pintype "bidirectional"))
      (node (ref "U$7") (pin "P$1") (pinfunction "P$1_P$1") (pintype "bidirectional"))
      (node (ref "U$9") (pin "P$1") (pinfunction "P$1_P$1") (pintype "bidirectional"))
      (node (ref "U1") (pin "2") (pinfunction "GND_2") (pintype "power_in"))
      (node (ref "U1") (pin "25") (pinfunction "GNDIO_25") (pintype "power_in"))
      (node (ref "U1") (pin "5") (pinfunction "PS1_5") (pintype "input"))
      (node (ref "U1") (pin "6") (pinfunction "PS0/WAKE_6") (pintype "input"))
      (node (ref "U2") (pin "2") (pinfunction "GND_2") (pintype "power_in"))
      (node (ref "U3") (pin "10") (pinfunction "VSS_2_10") (pintype "power_in"))
      (node (ref "U3") (pin "19") (pinfunction "VSSA_19") (pintype "power_in"))
      (node (ref "U3") (pin "26") (pinfunction "VSS_3_26") (pintype "power_in"))
      (node (ref "U3") (pin "49") (pinfunction "VSS_4_49") (pintype "power_in"))
      (node (ref "U3") (pin "74") (pinfunction "VSS_5_74") (pintype "power_in"))
      (node (ref "U3") (pin "99") (pinfunction "VSS_99") (pintype "power_in"))
      (node (ref "U33") (pin "2") (pinfunction "GND_2") (pintype "power_in"))
      (node (ref "U4") (pin "3") (pinfunction "VSS_2_3") (pintype "passive"))
      (node (ref "U4") (pin "5") (pinfunction "SDO_5") (pintype "passive"))
      (node (ref "U4") (pin "8") (pinfunction "VSS_3_8") (pintype "passive"))
      (node (ref "U4") (pin "9") (pinfunction "VSS_9") (pintype "passive"))
      (node (ref "U5") (pin "4") (pinfunction "GND_4") (pintype "power_in"))
    )
    (net (code "5") (name "MONITORING") (class "Default")
      (node (ref "C37") (pin "1") (pinfunction "1_1") (pintype "passive"))
      (node (ref "R9") (pin "2") (pinfunction "2_2") (pintype "passive"))
      (node (ref "U3") (pin "15") (pinfunction "PC0_15") (pintype "bidirectional"))
    )
    (net (code "6") (name "NRESET") (class "Default")
      (node (ref "C31") (pin "1") (pinfunction "1_1") (pintype "passive"))
      (node (ref "LORA") (pin "2") (pinfunction "2_2") (pintype "passive"))
      (node (ref "R1") (pin "2") (pinfunction "2_2") (pintype "passive"))
      (node (ref "RST") (pin "C") (pinfunction "COM_C") (pintype "passive"))
      (node (ref "SWD") (pin "5") (pinfunction "5_5") (pintype "bidirectional"))
      (node (ref "U1") (pin "11") (pinfunction "~{RST}_11") (pintype "input"))
      (node (ref "U3") (pin "14") (pinfunction "NRST_14") (pintype "bidirectional"))
    )
    (net (code "7") (name "Net-(BOOT-COM)") (class "Default")
      (node (ref "BOOT") (pin "C") (pinfunction "COM_C") (pintype "passive"))
      (node (ref "R10") (pin "2") (pinfunction "2_2") (pintype "passive"))
    )
    (net (code "8") (name "Net-(C10-Pad2)") (class "Default")
      (node (ref "C10") (pin "2") (pinfunction "2_2") (pintype "passive"))
      (node (ref "C8") (pin "2") (pinfunction "2_2") (pintype "passive"))
      (node (ref "C9") (pin "2") (pinfunction "2_2") (pintype "passive"))
      (node (ref "L2") (pin "1") (pinfunction "1_1") (pintype "passive"))
      (node (ref "LORA") (pin "1") (pinfunction "1_1") (pintype "passive"))
    )
    (net (code "9") (name "Net-(R14-Pad1)") (class "Default")
      (node (ref "R14") (pin "1") (pinfunction "1_1") (pintype "passive"))
      (node (ref "R15") (pin "2") (pinfunction "2_2") (pintype "passive"))
      (node (ref "R9") (pin "1") (pinfunction "1_1") (pintype "passive"))
    )
    (net (code "10") (name "Net-(U1-CAP)") (class "Default")
      (node (ref "C15") (pin "2") (pinfunction "2_2") (pintype "passive"))
      (node (ref "U1") (pin "9") (pinfunction "CAP_9") (pintype "passive"))
    )
    (net (code "11") (name "Net-(U1-SA0{slash}H_MOSI)") (class "Default")
      (node (ref "R4") (pin "2") (pinfunction "2_2") (pintype "passive"))
      (node (ref "U1") (pin "17") (pinfunction "SA0/H_MOSI_17") (pintype "input"))
    )
    (net (code "12") (name "Net-(U3B-BOOT0)") (class "Default")
      (node (ref "R10") (pin "1") (pinfunction "1_1") (pintype "passive"))
      (node (ref "U3") (pin "94") (pinfunction "BOOT0_94") (pintype "input"))
    )
    (net (code "13") (name "Net-(U3B-PH0-OSC_IN)") (class "Default")
      (node (ref "C1") (pin "1") (pinfunction "1_1") (pintype "passive"))
      (node (ref "CRYSTAL") (pin "P$3") (pinfunction "P$3_P$3") (pintype "bidirectional"))
      (node (ref "U3") (pin "12") (pinfunction "PH0-OSC_IN_12") (pintype "bidirectional"))
    )
    (net (code "14") (name "Net-(U3B-PH1-OSC_OUT)") (class "Default")
      (node (ref "C2") (pin "1") (pinfunction "1_1") (pintype "passive"))
      (node (ref "CRYSTAL") (pin "P$1") (pinfunction "P$1_P$1") (pintype "bidirectional"))
      (node (ref "U3") (pin "13") (pinfunction "PH1-OSC_OUT_13") (pintype "bidirectional"))
    )
    (net (code "15") (name "Net-(U3C-VCAP1)") (class "Default")
      (node (ref "C4") (pin "1") (pinfunction "1_1") (pintype "passive"))
      (node (ref "U3") (pin "48") (pinfunction "VCAP1_48") (pintype "power_in"))
    )
    (net (code "16") (name "Net-(U3C-VCAP2)") (class "Default")
      (node (ref "C5") (pin "1") (pinfunction "1_1") (pintype "passive"))
      (node (ref "U3") (pin "73") (pinfunction "VCAP2_73") (pintype "power_in"))
    )
    (net (code "17") (name "Net-(U5-BST)") (class "Default")
      (node (ref "C34") (pin "2") (pinfunction "2_2") (pintype "passive"))
      (node (ref "U5") (pin "6") (pinfunction "BST_6") (pintype "input"))
    )
    (net (code "18") (name "Net-(U5-FB)") (class "Default")
      (node (ref "C33") (pin "1") (pinfunction "1_1") (pintype "passive"))
      (node (ref "R11") (pin "1") (pinfunction "1_1") (pintype "passive"))
      (node (ref "R12") (pin "2") (pinfunction "2_2") (pintype "passive"))
      (node (ref "U5") (pin "1") (pinfunction "FB_1") (pintype "input"))
    )
    (net (code "19") (name "Net-(U5-SW)") (class "Default")
      (node (ref "C34") (pin "1") (pinfunction "1_1") (pintype "passive"))
      (node (ref "L1") (pin "2") (pinfunction "2_2") (pintype "passive"))
      (node (ref "U5") (pin "5") (pinfunction "SW_5") (pintype "output"))
    )
    (net (code "20") (name "PA0") (class "Default")
      (node (ref "PWM-IN") (pin "1") (pinfunction "1_1") (pintype "bidirectional"))
      (node (ref "U3") (pin "22") (pinfunction "PA0-WKUP_22") (pintype "bidirectional"))
    )
    (net (code "21") (name "PA1") (class "Default")
      (node (ref "U$12") (pin "1") (pinfunction "1_1") (pintype "bidirectional"))
      (node (ref "U3") (pin "23") (pinfunction "PA1_23") (pintype "bidirectional"))
    )
    (net (code "22") (name "PA2") (class "Default")
      (node (ref "U$12") (pin "2") (pinfunction "2_2") (pintype "bidirectional"))
      (node (ref "U3") (pin "24") (pinfunction "PA2_24") (pintype "bidirectional"))
    )
    (net (code "23") (name "PA3") (class "Default")
      (node (ref "U$12") (pin "3") (pinfunction "3_3") (pintype "bidirectional"))
      (node (ref "U3") (pin "25") (pinfunction "PA3_25") (pintype "bidirectional"))
    )
    (net (code "24") (name "PA4") (class "Default")
      (node (ref "JP2") (pin "1") (pinfunction "1_1") (pintype "passive"))
      (node (ref "U3") (pin "28") (pinfunction "PA4_28") (pintype "bidirectional"))
    )
    (net (code "25") (name "PA5") (class "Default")
      (node (ref "PWM-IN") (pin "3") (pinfunction "3_3") (pintype "bidirectional"))
      (node (ref "U3") (pin "29") (pinfunction "PA5_29") (pintype "bidirectional"))
    )
    (net (code "26") (name "PA6") (class "Default")
      (node (ref "PWM-IN") (pin "5") (pinfunction "5_5") (pintype "bidirectional"))
      (node (ref "U3") (pin "30") (pinfunction "PA6_30") (pintype "bidirectional"))
    )
    (net (code "27") (name "PA7") (class "Default")
      (node (ref "JP2") (pin "2") (pinfunction "2_2") (pintype "passive"))
      (node (ref "U3") (pin "31") (pinfunction "PA7_31") (pintype "bidirectional"))
    )
    (net (code "28") (name "PA8") (class "Default")
      (node (ref "JP1") (pin "14") (pinfunction "14_14") (pintype "passive"))
      (node (ref "U3") (pin "67") (pinfunction "PA8_67") (pintype "bidirectional"))
    )
    (net (code "29") (name "PA9") (class "Default")
      (node (ref "JP1") (pin "15") (pinfunction "15_15") (pintype "passive"))
      (node (ref "U3") (pin "68") (pinfunction "PA9_68") (pintype "bidirectional"))
    )
    (net (code "30") (name "PA10") (class "Default")
      (node (ref "JP1") (pin "16") (pinfunction "16_16") (pintype "passive"))
      (node (ref "U3") (pin "69") (pinfunction "PA10_69") (pintype "bidirectional"))
    )
    (net (code "31") (name "PA11") (class "Default")
      (node (ref "U$14") (pin "2") (pinfunction "2_2") (pintype "bidirectional"))
      (node (ref "U3") (pin "70") (pinfunction "PA11_70") (pintype "bidirectional"))
    )
    (net (code "32") (name "PA12") (class "Default")
      (node (ref "U$14") (pin "1") (pinfunction "1_1") (pintype "bidirectional"))
      (node (ref "U3") (pin "71") (pinfunction "PA12_71") (pintype "bidirectional"))
    )
    (net (code "33") (name "PB0") (class "Default")
      (node (ref "JP2") (pin "5") (pinfunction "5_5") (pintype "passive"))
      (node (ref "U3") (pin "34") (pinfunction "PB0_34") (pintype "bidirectional"))
    )
    (net (code "34") (name "PB1") (class "Default")
      (node (ref "JP2") (pin "6") (pinfunction "6_6") (pintype "passive"))
      (node (ref "U3") (pin "35") (pinfunction "PB1_35") (pintype "bidirectional"))
    )
    (net (code "35") (name "PB2") (class "Default")
      (node (ref "JP2") (pin "7") (pinfunction "7_7") (pintype "passive"))
      (node (ref "U3") (pin "36") (pinfunction "PB2_36") (pintype "bidirectional"))
    )
    (net (code "36") (name "PB5") (class "Default")
      (node (ref "JP3") (pin "2") (pinfunction "2_2") (pintype "passive"))
      (node (ref "U3") (pin "91") (pinfunction "PB5_91") (pintype "bidirectional"))
    )
    (net (code "37") (name "PB6") (class "Default")
      (node (ref "JP3") (pin "1") (pinfunction "1_1") (pintype "passive"))
      (node (ref "U3") (pin "92") (pinfunction "PB6_92") (pintype "bidirectional"))
    )
    (net (code "38") (name "PB12") (class "Default")
      (node (ref "JP1") (pin "1") (pinfunction "1_1") (pintype "passive"))
      (node (ref "U3") (pin "51") (pinfunction "PB12_51") (pintype "bidirectional"))
    )
    (net (code "39") (name "PB13") (class "Default")
      (node (ref "JP1") (pin "2") (pinfunction "2_2") (pintype "passive"))
      (node (ref "U3") (pin "52") (pinfunction "PB13_52") (pintype "bidirectional"))
    )
    (net (code "40") (name "PB13_2") (class "Default")
      (node (ref "JP2") (pin "14") (pinfunction "14_14") (pintype "passive"))
      (node (ref "U3") (pin "43") (pinfunction "PB13_2_43") (pintype "bidirectional"))
    )
    (net (code "41") (name "PB14") (class "Default")
      (node (ref "JP1") (pin "3") (pinfunction "3_3") (pintype "passive"))
      (node (ref "U3") (pin "53") (pinfunction "PB14_53") (pintype "bidirectional"))
    )
    (net (code "42") (name "PB14_2") (class "Default")
      (node (ref "JP2") (pin "15") (pinfunction "15_15") (pintype "passive"))
      (node (ref "U3") (pin "44") (pinfunction "PB14_2_44") (pintype "bidirectional"))
    )
    (net (code "43") (name "PB15") (class "Default")
      (node (ref "PWM-OUT") (pin "7") (pinfunction "7_7") (pintype "bidirectional"))
      (node (ref "U3") (pin "54") (pinfunction "PB15_54") (pintype "bidirectional"))
    )
    (net (code "44") (name "PC1") (class "Default")
      (node (ref "U$13") (pin "1") (pinfunction "1_1") (pintype "bidirectional"))
      (node (ref "U3") (pin "16") (pinfunction "PC1_16") (pintype "bidirectional"))
    )
    (net (code "45") (name "PC2") (class "Default")
      (node (ref "U$13") (pin "2") (pinfunction "2_2") (pintype "bidirectional"))
      (node (ref "U3") (pin "17") (pinfunction "PC2_17") (pintype "bidirectional"))
    )
    (net (code "46") (name "PC3") (class "Default")
      (node (ref "U$13") (pin "3") (pinfunction "3_3") (pintype "bidirectional"))
      (node (ref "U3") (pin "18") (pinfunction "PC3_18") (pintype "bidirectional"))
    )
    (net (code "47") (name "PC4") (class "Default")
      (node (ref "JP2") (pin "3") (pinfunction "3_3") (pintype "passive"))
      (node (ref "U3") (pin "32") (pinfunction "PC4_32") (pintype "bidirectional"))
    )
    (net (code "48") (name "PC5") (class "Default")
      (node (ref "JP2") (pin "4") (pinfunction "4_4") (pintype "passive"))
      (node (ref "U3") (pin "33") (pinfunction "PC5_33") (pintype "bidirectional"))
    )
    (net (code "49") (name "PC6") (class "Default")
      (node (ref "PWM-OUT") (pin "3") (pinfunction "3_3") (pintype "bidirectional"))
      (node (ref "U3") (pin "63") (pinfunction "PC6_63") (pintype "bidirectional"))
    )
    (net (code "50") (name "PC7") (class "Default")
      (node (ref "JP1") (pin "11") (pinfunction "11_11") (pintype "passive"))
      (node (ref "U3") (pin "64") (pinfunction "PC7_64") (pintype "bidirectional"))
    )
    (net (code "51") (name "PC8") (class "Default")
      (node (ref "JP1") (pin "12") (pinfunction "12_12") (pintype "passive"))
      (node (ref "U3") (pin "65") (pinfunction "PC8_65") (pintype "bidirectional"))
    )
    (net (code "52") (name "PC9") (class "Default")
      (node (ref "JP1") (pin "13") (pinfunction "13_13") (pintype "passive"))
      (node (ref "U3") (pin "66") (pinfunction "PC9_66") (pintype "bidirectional"))
    )
    (net (code "53") (name "PC10") (class "Default")
      (node (ref "JP3") (pin "13") (pinfunction "13_13") (pintype "passive"))
      (node (ref "U3") (pin "78") (pinfunction "PC10_78") (pintype "bidirectional"))
    )
    (net (code "54") (name "PC11") (class "Default")
      (node (ref "JP3") (pin "12") (pinfunction "12_12") (pintype "passive"))
      (node (ref "U3") (pin "79") (pinfunction "PC11_79") (pintype "bidirectional"))
    )
    (net (code "55") (name "PC12") (class "Default")
      (node (ref "JP3") (pin "11") (pinfunction "11_11") (pintype "passive"))
      (node (ref "U3") (pin "80") (pinfunction "PC12_80") (pintype "bidirectional"))
    )
    (net (code "56") (name "PD0") (class "Default")
      (node (ref "INT") (pin "TP") (pinfunction "TP_TP") (pintype "input"))
      (node (ref "U1") (pin "14") (pinfunction "~{H_INT}_14") (pintype "output"))
      (node (ref "U3") (pin "81") (pinfunction "PD0_81") (pintype "bidirectional"))
    )
    (net (code "57") (name "PD1") (class "Default")
      (node (ref "TP1") (pin "TP") (pinfunction "TP_TP") (pintype "input"))
      (node (ref "U3") (pin "82") (pinfunction "PD1_82") (pintype "bidirectional"))
      (node (ref "U4") (pin "7") (pinfunction "INT_7") (pintype "input"))
    )
    (net (code "58") (name "PD2") (class "Default")
      (node (ref "JP3") (pin "8") (pinfunction "8_8") (pintype "passive"))
      (node (ref "U3") (pin "83") (pinfunction "PD2_83") (pintype "bidirectional"))
    )
    (net (code "59") (name "PD3") (class "Default")
      (node (ref "JP3") (pin "7") (pinfunction "7_7") (pintype "passive"))
      (node (ref "U3") (pin "84") (pinfunction "PD3_84") (pintype "bidirectional"))
    )
    (net (code "60") (name "PD4") (class "Default")
      (node (ref "JP3") (pin "6") (pinfunction "6_6") (pintype "passive"))
      (node (ref "U3") (pin "85") (pinfunction "PD4_85") (pintype "bidirectional"))
    )
    (net (code "61") (name "PD5") (class "Default")
      (node (ref "JP3") (pin "5") (pinfunction "5_5") (pintype "passive"))
      (node (ref "U3") (pin "86") (pinfunction "PD5_86") (pintype "bidirectional"))
    )
    (net (code "62") (name "PD6") (class "Default")
      (node (ref "JP3") (pin "4") (pinfunction "4_4") (pintype "passive"))
      (node (ref "U3") (pin "87") (pinfunction "PD6_87") (pintype "bidirectional"))
    )
    (net (code "63") (name "PD7") (class "Default")
      (node (ref "JP3") (pin "3") (pinfunction "3_3") (pintype "passive"))
      (node (ref "U3") (pin "88") (pinfunction "PD7_88") (pintype "bidirectional"))
    )
    (net (code "64") (name "PD8") (class "Default")
      (node (ref "JP1") (pin "4") (pinfunction "4_4") (pintype "passive"))
      (node (ref "U3") (pin "55") (pinfunction "PD8_55") (pintype "bidirectional"))
    )
    (net (code "65") (name "PD9") (class "Default")
      (node (ref "JP1") (pin "5") (pinfunction "5_5") (pintype "passive"))
      (node (ref "U3") (pin "56") (pinfunction "PD9_56") (pintype "bidirectional"))
    )
    (net (code "66") (name "PD10") (class "Default")
      (node (ref "JP1") (pin "6") (pinfunction "6_6") (pintype "passive"))
      (node (ref "U3") (pin "57") (pinfunction "PD10_57") (pintype "bidirectional"))
    )
    (net (code "67") (name "PD11") (class "Default")
      (node (ref "JP1") (pin "7") (pinfunction "7_7") (pintype "passive"))
      (node (ref "U3") (pin "58") (pinfunction "PD11_58") (pintype "bidirectional"))
    )
    (net (code "68") (name "PD12") (class "Default")
      (node (ref "PWM-IN") (pin "7") (pinfunction "7_7") (pintype "bidirectional"))
      (node (ref "U3") (pin "59") (pinfunction "PD12_59") (pintype "bidirectional"))
    )
    (net (code "69") (name "PD13") (class "Default")
      (node (ref "JP1") (pin "8") (pinfunction "8_8") (pintype "passive"))
      (node (ref "U3") (pin "60") (pinfunction "PD13_60") (pintype "bidirectional"))
    )
    (net (code "70") (name "PD14") (class "Default")
      (node (ref "JP1") (pin "9") (pinfunction "9_9") (pintype "passive"))
      (node (ref "U3") (pin "61") (pinfunction "PD14_61") (pintype "bidirectional"))
    )
    (net (code "71") (name "PD15") (class "Default")
      (node (ref "JP1") (pin "10") (pinfunction "10_10") (pintype "passive"))
      (node (ref "U3") (pin "62") (pinfunction "PD15_62") (pintype "bidirectional"))
    )
    (net (code "72") (name "PE2") (class "Default")
      (node (ref "U$1") (pin "1") (pinfunction "1_1") (pintype "bidirectional"))
      (node (ref "U3") (pin "1") (pinfunction "PE2_1") (pintype "bidirectional"))
    )
    (net (code "73") (name "PE3") (class "Default")
      (node (ref "U$1") (pin "2") (pinfunction "2_2") (pintype "bidirectional"))
      (node (ref "U3") (pin "2") (pinfunction "PE3_2") (pintype "bidirectional"))
    )
    (net (code "74") (name "PE4") (class "Default")
      (node (ref "U$1") (pin "3") (pinfunction "3_3") (pintype "bidirectional"))
      (node (ref "U3") (pin "3") (pinfunction "PE4_3") (pintype "bidirectional"))
    )
    (net (code "75") (name "PE5") (class "Default")
      (node (ref "PWM-OUT") (pin "5") (pinfunction "5_5") (pintype "bidirectional"))
      (node (ref "U3") (pin "4") (pinfunction "PE5_4") (pintype "bidirectional"))
    )
    (net (code "76") (name "PE6") (class "Default")
      (node (ref "U$1") (pin "4") (pinfunction "4_4") (pintype "bidirectional"))
      (node (ref "U3") (pin "5") (pinfunction "PE6_5") (pintype "bidirectional"))
    )
    (net (code "77") (name "PE7") (class "Default")
      (node (ref "JP2") (pin "8") (pinfunction "8_8") (pintype "passive"))
      (node (ref "U3") (pin "37") (pinfunction "PE7_37") (pintype "bidirectional"))
    )
    (net (code "78") (name "PE8") (class "Default")
      (node (ref "JP2") (pin "9") (pinfunction "9_9") (pintype "passive"))
      (node (ref "U3") (pin "38") (pinfunction "PE8_38") (pintype "bidirectional"))
    )
    (net (code "79") (name "PE9") (class "Default")
      (node (ref "PWM-OUT") (pin "1") (pinfunction "1_1") (pintype "bidirectional"))
      (node (ref "U3") (pin "39") (pinfunction "PE9_39") (pintype "bidirectional"))
    )
    (net (code "80") (name "PE10") (class "Default")
      (node (ref "JP2") (pin "11") (pinfunction "11_11") (pintype "passive"))
      (node (ref "U3") (pin "40") (pinfunction "PE10_40") (pintype "bidirectional"))
    )
    (net (code "81") (name "PE11") (class "Default")
      (node (ref "JP2") (pin "12") (pinfunction "12_12") (pintype "passive"))
      (node (ref "U3") (pin "41") (pinfunction "PE11_41") (pintype "bidirectional"))
    )
    (net (code "82") (name "PE12") (class "Default")
      (node (ref "JP2") (pin "13") (pinfunction "13_13") (pintype "passive"))
      (node (ref "U3") (pin "42") (pinfunction "PE12_42") (pintype "bidirectional"))
    )
    (net (code "83") (name "PE15") (class "Default")
      (node (ref "JP2") (pin "16") (pinfunction "16_16") (pintype "passive"))
      (node (ref "U3") (pin "45") (pinfunction "PE15_45") (pintype "bidirectional"))
    )
    (net (code "84") (name "RXD") (class "Default")
      (node (ref "LORA") (pin "4") (pinfunction "4_4") (pintype "passive"))
      (node (ref "U3") (pin "97") (pinfunction "PE0_97") (pintype "bidirectional"))
    )
    (net (code "85") (name "SCL") (class "Default")
      (node (ref "R17") (pin "1") (pinfunction "1_1") (pintype "passive"))
      (node (ref "SCL0") (pin "TP") (pinfunction "TP_TP") (pintype "input"))
      (node (ref "U1") (pin "19") (pinfunction "H_SCL/SCK/RX_19") (pintype "bidirectional"))
      (node (ref "U3") (pin "46") (pinfunction "PB10_46") (pintype "bidirectional"))
    )
    (net (code "86") (name "SCL1") (class "Default")
      (node (ref "R8") (pin "2") (pinfunction "2_2") (pintype "passive"))
      (node (ref "SCL1") (pin "TP") (pinfunction "TP_TP") (pintype "input"))
      (node (ref "U3") (pin "95") (pinfunction "PB8_95") (pintype "bidirectional"))
      (node (ref "U4") (pin "2") (pinfunction "SCK_2") (pintype "passive"))
    )
    (net (code "87") (name "SDA1") (class "Default")
      (node (ref "R7") (pin "2") (pinfunction "2_2") (pintype "passive"))
      (node (ref "SDA1") (pin "TP") (pinfunction "TP_TP") (pintype "input"))
      (node (ref "U3") (pin "93") (pinfunction "PB7_93") (pintype "bidirectional"))
      (node (ref "U4") (pin "4") (pinfunction "SDI_4") (pintype "passive"))
    )
    (net (code "88") (name "SDA{slash}BNO") (class "Default")
      (node (ref "R16") (pin "1") (pinfunction "1_1") (pintype "passive"))
      (node (ref "SDA0") (pin "TP") (pinfunction "TP_TP") (pintype "input"))
      (node (ref "U1") (pin "20") (pinfunction "H_SDA/H_MISO/TX_20") (pintype "bidirectional"))
      (node (ref "U3") (pin "47") (pinfunction "PB11_47") (pintype "bidirectional"))
    )
    (net (code "89") (name "TCK{slash}SWCLK") (class "Default")
      (node (ref "SWD") (pin "2") (pinfunction "2_2") (pintype "bidirectional"))
      (node (ref "U3") (pin "76") (pinfunction "PA14_76") (pintype "bidirectional"))
    )
    (net (code "90") (name "TDO{slash}SWO") (class "Default")
      (node (ref "SWD") (pin "6") (pinfunction "6_6") (pintype "bidirectional"))
      (node (ref "U3") (pin "89") (pinfunction "PB3_89") (pintype "bidirectional"))
    )
    (net (code "91") (name "TMS{slash}SWDIO") (class "Default")
      (node (ref "SWD") (pin "4") (pinfunction "4_4") (pintype "bidirectional"))
      (node (ref "U3") (pin "72") (pinfunction "PA13_72") (pintype "bidirectional"))
    )
    (net (code "92") (name "TXD") (class "Default")
      (node (ref "LORA") (pin "3") (pinfunction "3_3") (pintype "passive"))
      (node (ref "U3") (pin "98") (pinfunction "PE1_98") (pintype "bidirectional"))
    )
    (net (code "93") (name "V3P3A") (class "Default")
      (node (ref "BOOT") (pin "3") (pinfunction "NO_3") (pintype "passive"))
      (node (ref "C12") (pin "2") (pinfunction "2_2") (pintype "passive"))
      (node (ref "C21") (pin "1") (pinfunction "1_1") (pintype "passive"))
      (node (ref "C22") (pin "1") (pinfunction "1_1") (pintype "passive"))
      (node (ref "C23") (pin "2") (pinfunction "2_2") (pintype "passive"))
      (node (ref "C27") (pin "2") (pinfunction "2_2") (pintype "passive"))
      (node (ref "C28") (pin "2") (pinfunction "2_2") (pintype "passive"))
      (node (ref "C29") (pin "1") (pinfunction "1_1") (pintype "passive"))
      (node (ref "C3") (pin "1") (pinfunction "1_1") (pintype "passive"))
      (node (ref "C30") (pin "1") (pinfunction "1_1") (pintype "passive"))
      (node (ref "C38") (pin "1") (pinfunction "1_1") (pintype "passive"))
      (node (ref "C39") (pin "2") (pinfunction "2_2") (pintype "passive"))
      (node (ref "C40") (pin "2") (pinfunction "2_2") (pintype "passive"))
      (node (ref "D3") (pin "2") (pinfunction "A_2") (pintype "passive"))
      (node (ref "JP4") (pin "1") (pinfunction "1_1") (pintype "passive"))
      (node (ref "JP4") (pin "3") (pinfunction "3_3") (pintype "passive"))
      (node (ref "JP4") (pin "5") (pinfunction "5_5") (pintype "passive"))
      (node (ref "JP4") (pin "7") (pinfunction "7_7") (pintype "passive"))
      (node (ref "JP4") (pin "9") (pinfunction "9_9") (pintype "passive"))
      (node (ref "R7") (pin "1") (pinfunction "1_1") (pintype "passive"))
      (node (ref "R8") (pin "1") (pinfunction "1_1") (pintype "passive"))
      (node (ref "SWD") (pin "1") (pinfunction "1_1") (pintype "bidirectional"))
      (node (ref "TP3") (pin "TP") (pinfunction "TP_TP") (pintype "input"))
      (node (ref "U2") (pin "5") (pinfunction "OUT_5") (pintype "passive"))
      (node (ref "U3") (pin "100") (pinfunction "VDD_100") (pintype "power_in"))
      (node (ref "U3") (pin "11") (pinfunction "VDD_2_11") (pintype "power_in"))
      (node (ref "U3") (pin "20") (pinfunction "VREF+_20") (pintype "power_in"))
      (node (ref "U3") (pin "21") (pinfunction "VDDA_21") (pintype "power_in"))
      (node (ref "U3") (pin "27") (pinfunction "VDD_3_27") (pintype "power_in"))
      (node (ref "U3") (pin "50") (pinfunction "VDD_4_50") (pintype "power_in"))
      (node (ref "U3") (pin "6") (pinfunction "VBAT_6") (pintype "power_in"))
      (node (ref "U3") (pin "75") (pinfunction "VDD_5_75") (pintype "power_in"))
      (node (ref "U4") (pin "1") (pinfunction "VDDIO_1") (pintype "power_in"))
      (node (ref "U4") (pin "10") (pinfunction "VDD_10") (pintype "power_in"))
      (node (ref "U4") (pin "6") (pinfunction "CSB_6") (pintype "passive"))
    )
    (net (code "94") (name "V3P3B") (class "Default")
      (node (ref "C13") (pin "2") (pinfunction "2_2") (pintype "passive"))
      (node (ref "C14") (pin "2") (pinfunction "2_2") (pintype "passive"))
      (node (ref "C36") (pin "2") (pinfunction "2_2") (pintype "passive"))
      (node (ref "C7") (pin "2") (pinfunction "2_2") (pintype "passive"))
      (node (ref "D2") (pin "2") (pinfunction "A_2") (pintype "passive"))
      (node (ref "JP6") (pin "1") (pinfunction "1_1") (pintype "passive"))
      (node (ref "JP6") (pin "3") (pinfunction "3_3") (pintype "passive"))
      (node (ref "JP6") (pin "5") (pinfunction "5_5") (pintype "passive"))
      (node (ref "JP6") (pin "7") (pinfunction "7_7") (pintype "passive"))
      (node (ref "JP6") (pin "9") (pinfunction "9_9") (pintype "passive"))
      (node (ref "L2") (pin "2") (pinfunction "2_2") (pintype "passive"))
      (node (ref "R1") (pin "1") (pinfunction "1_1") (pintype "passive"))
      (node (ref "R16") (pin "2") (pinfunction "2_2") (pintype "passive"))
      (node (ref "R17") (pin "2") (pinfunction "2_2") (pintype "passive"))
      (node (ref "R6") (pin "2") (pinfunction "2_2") (pintype "passive"))
      (node (ref "U1") (pin "10") (pinfunction "CLKSEL0_10") (pintype "input"))
      (node (ref "U1") (pin "28") (pinfunction "VDDIO_28") (pintype "power_in"))
      (node (ref "U1") (pin "3") (pinfunction "VDD_3") (pintype "power_in"))
      (node (ref "U33") (pin "5") (pinfunction "OUT_5") (pintype "passive"))
    )
    (net (code "95") (name "V5") (class "Default")
      (node (ref "C11") (pin "2") (pinfunction "2_2") (pintype "passive"))
      (node (ref "C2A") (pin "1") (pinfunction "1_1") (pintype "passive"))
      (node (ref "C2B") (pin "1") (pinfunction "1_1") (pintype "passive"))
      (node (ref "C33") (pin "2") (pinfunction "2_2") (pintype "passive"))
      (node (ref "C35") (pin "2") (pinfunction "2_2") (pintype "passive"))
      (node (ref "D2") (pin "1") (pinfunction "C_1") (pintype "passive"))
      (node (ref "D3") (pin "1") (pinfunction "C_1") (pintype "passive"))
      (node (ref "JP5") (pin "1") (pinfunction "1_1") (pintype "passive"))
      (node (ref "JP5") (pin "3") (pinfunction "3_3") (pintype "passive"))
      (node (ref "JP5") (pin "5") (pinfunction "5_5") (pintype "passive"))
      (node (ref "JP5") (pin "7") (pinfunction "7_7") (pintype "passive"))
      (node (ref "JP5") (pin "9") (pinfunction "9_9") (pintype "passive"))
      (node (ref "L1") (pin "1") (pinfunction "1_1") (pintype "passive"))
      (node (ref "R11") (pin "2") (pinfunction "2_2") (pintype "passive"))
      (node (ref "U2") (pin "1") (pinfunction "IN_1") (pintype "power_in"))
      (node (ref "U2") (pin "3") (pinfunction "EN_3") (pintype "input"))
      (node (ref "U33") (pin "1") (pinfunction "IN_1") (pintype "power_in"))
      (node (ref "U33") (pin "3") (pinfunction "EN_3") (pintype "input"))
    )
    (net (code "96") (name "unconnected-(JP2-Pad10)") (class "Default")
      (node (ref "JP2") (pin "10") (pinfunction "10_10") (pintype "passive"))
    )
    (net (code "97") (name "unconnected-(JP3-Pad9)") (class "Default")
      (node (ref "JP3") (pin "9") (pinfunction "9_9") (pintype "passive"))
    )
    (net (code "98") (name "unconnected-(JP3-Pad10)") (class "Default")
      (node (ref "JP3") (pin "10") (pinfunction "10_10") (pintype "passive"))
    )
    (net (code "99") (name "unconnected-(JP3-Pad14)") (class "Default")
      (node (ref "JP3") (pin "14") (pinfunction "14_14") (pintype "passive"))
    )
    (net (code "100") (name "unconnected-(RST-NC-Pad1)") (class "Default")
      (node (ref "RST") (pin "1") (pinfunction "NC_1") (pintype "passive"))
    )
    (net (code "101") (name "unconnected-(U1-ENV_SCL-Pad15)") (class "Default")
      (node (ref "U1") (pin "15") (pinfunction "ENV_SCL_15") (pintype "bidirectional"))
    )
    (net (code "102") (name "unconnected-(U1-ENV_SDA-Pad16)") (class "Default")
      (node (ref "U1") (pin "16") (pinfunction "ENV_SDA_16") (pintype "bidirectional"))
    )
    (net (code "103") (name "unconnected-(U1-RESV_NC-Pad1)") (class "Default")
      (node (ref "U1") (pin "1") (pinfunction "RESV_NC_1") (pintype "no_connect"))
    )
    (net (code "104") (name "unconnected-(U1-RESV_NC-Pad7)") (class "Default")
      (node (ref "U1") (pin "7") (pinfunction "RESV_NC_7") (pintype "no_connect"))
    )
    (net (code "105") (name "unconnected-(U1-RESV_NC-Pad8)") (class "Default")
      (node (ref "U1") (pin "8") (pinfunction "RESV_NC_8") (pintype "no_connect"))
    )
    (net (code "106") (name "unconnected-(U1-RESV_NC-Pad12)") (class "Default")
      (node (ref "U1") (pin "12") (pinfunction "RESV_NC_12") (pintype "no_connect"))
    )
    (net (code "107") (name "unconnected-(U1-RESV_NC-Pad13)") (class "Default")
      (node (ref "U1") (pin "13") (pinfunction "RESV_NC_13") (pintype "no_connect"))
    )
    (net (code "108") (name "unconnected-(U1-RESV_NC-Pad21)") (class "Default")
      (node (ref "U1") (pin "21") (pinfunction "RESV_NC_21") (pintype "no_connect"))
    )
    (net (code "109") (name "unconnected-(U1-RESV_NC-Pad22)") (class "Default")
      (node (ref "U1") (pin "22") (pinfunction "RESV_NC_22") (pintype "no_connect"))
    )
    (net (code "110") (name "unconnected-(U1-RESV_NC-Pad23)") (class "Default")
      (node (ref "U1") (pin "23") (pinfunction "RESV_NC_23") (pintype "no_connect"))
    )
    (net (code "111") (name "unconnected-(U1-RESV_NC-Pad24)") (class "Default")
      (node (ref "U1") (pin "24") (pinfunction "RESV_NC_24") (pintype "no_connect"))
    )
    (net (code "112") (name "unconnected-(U1-XIN32-Pad27)") (class "Default")
      (node (ref "U1") (pin "27") (pinfunction "XIN32_27") (pintype "input"))
    )
    (net (code "113") (name "unconnected-(U1-XOUT32{slash}CLKSEL1-Pad26)") (class "Default")
      (node (ref "U1") (pin "26") (pinfunction "XOUT32/CLKSEL1_26") (pintype "output"))
    )
    (net (code "114") (name "unconnected-(U1-~{H_CS}-Pad18)") (class "Default")
      (node (ref "U1") (pin "18") (pinfunction "~{H_CS}_18") (pintype "input"))
    )
    (net (code "115") (name "unconnected-(U2-EP-Pad8)") (class "Default")
      (node (ref "U2") (pin "8") (pinfunction "EP_8") (pintype "passive"))
    )
    (net (code "116") (name "unconnected-(U2-NC-Pad4)") (class "Default")
      (node (ref "U2") (pin "4") (pinfunction "NC_4") (pintype "passive"))
    )
    (net (code "117") (name "unconnected-(U3A-PB4-Pad90)") (class "Default")
      (node (ref "U3") (pin "90") (pinfunction "PB4_90") (pintype "bidirectional"))
    )
    (net (code "118") (name "unconnected-(U3A-PB9-Pad96)") (class "Default")
      (node (ref "U3") (pin "96") (pinfunction "PB9_96") (pintype "bidirectional"))
    )
    (net (code "119") (name "unconnected-(U3A-PC13-ANTI_TAMP-Pad7)") (class "Default")
      (node (ref "U3") (pin "7") (pinfunction "PC13-ANTI_TAMP_7") (pintype "bidirectional"))
    )
    (net (code "120") (name "unconnected-(U3A-PC14-OSC32_IN-Pad8)") (class "Default")
      (node (ref "U3") (pin "8") (pinfunction "PC14-OSC32_IN_8") (pintype "bidirectional"))
    )
    (net (code "121") (name "unconnected-(U3A-PC15-OSC32_OUT-Pad9)") (class "Default")
      (node (ref "U3") (pin "9") (pinfunction "PC15-OSC32_OUT_9") (pintype "bidirectional"))
    )
    (net (code "122") (name "unconnected-(U33-EP-Pad8)") (class "Default")
      (node (ref "U33") (pin "8") (pinfunction "EP_8") (pintype "passive"))
    )
    (net (code "123") (name "unconnected-(U33-NC-Pad4)") (class "Default")
      (node (ref "U33") (pin "4") (pinfunction "NC_4") (pintype "passive"))
    )
  )
)
